# RELAY_CONTACT_BOUNCE_ELIMINATOR_REV_2.net
KiCad netlist of a schematic drawn in EAGLE
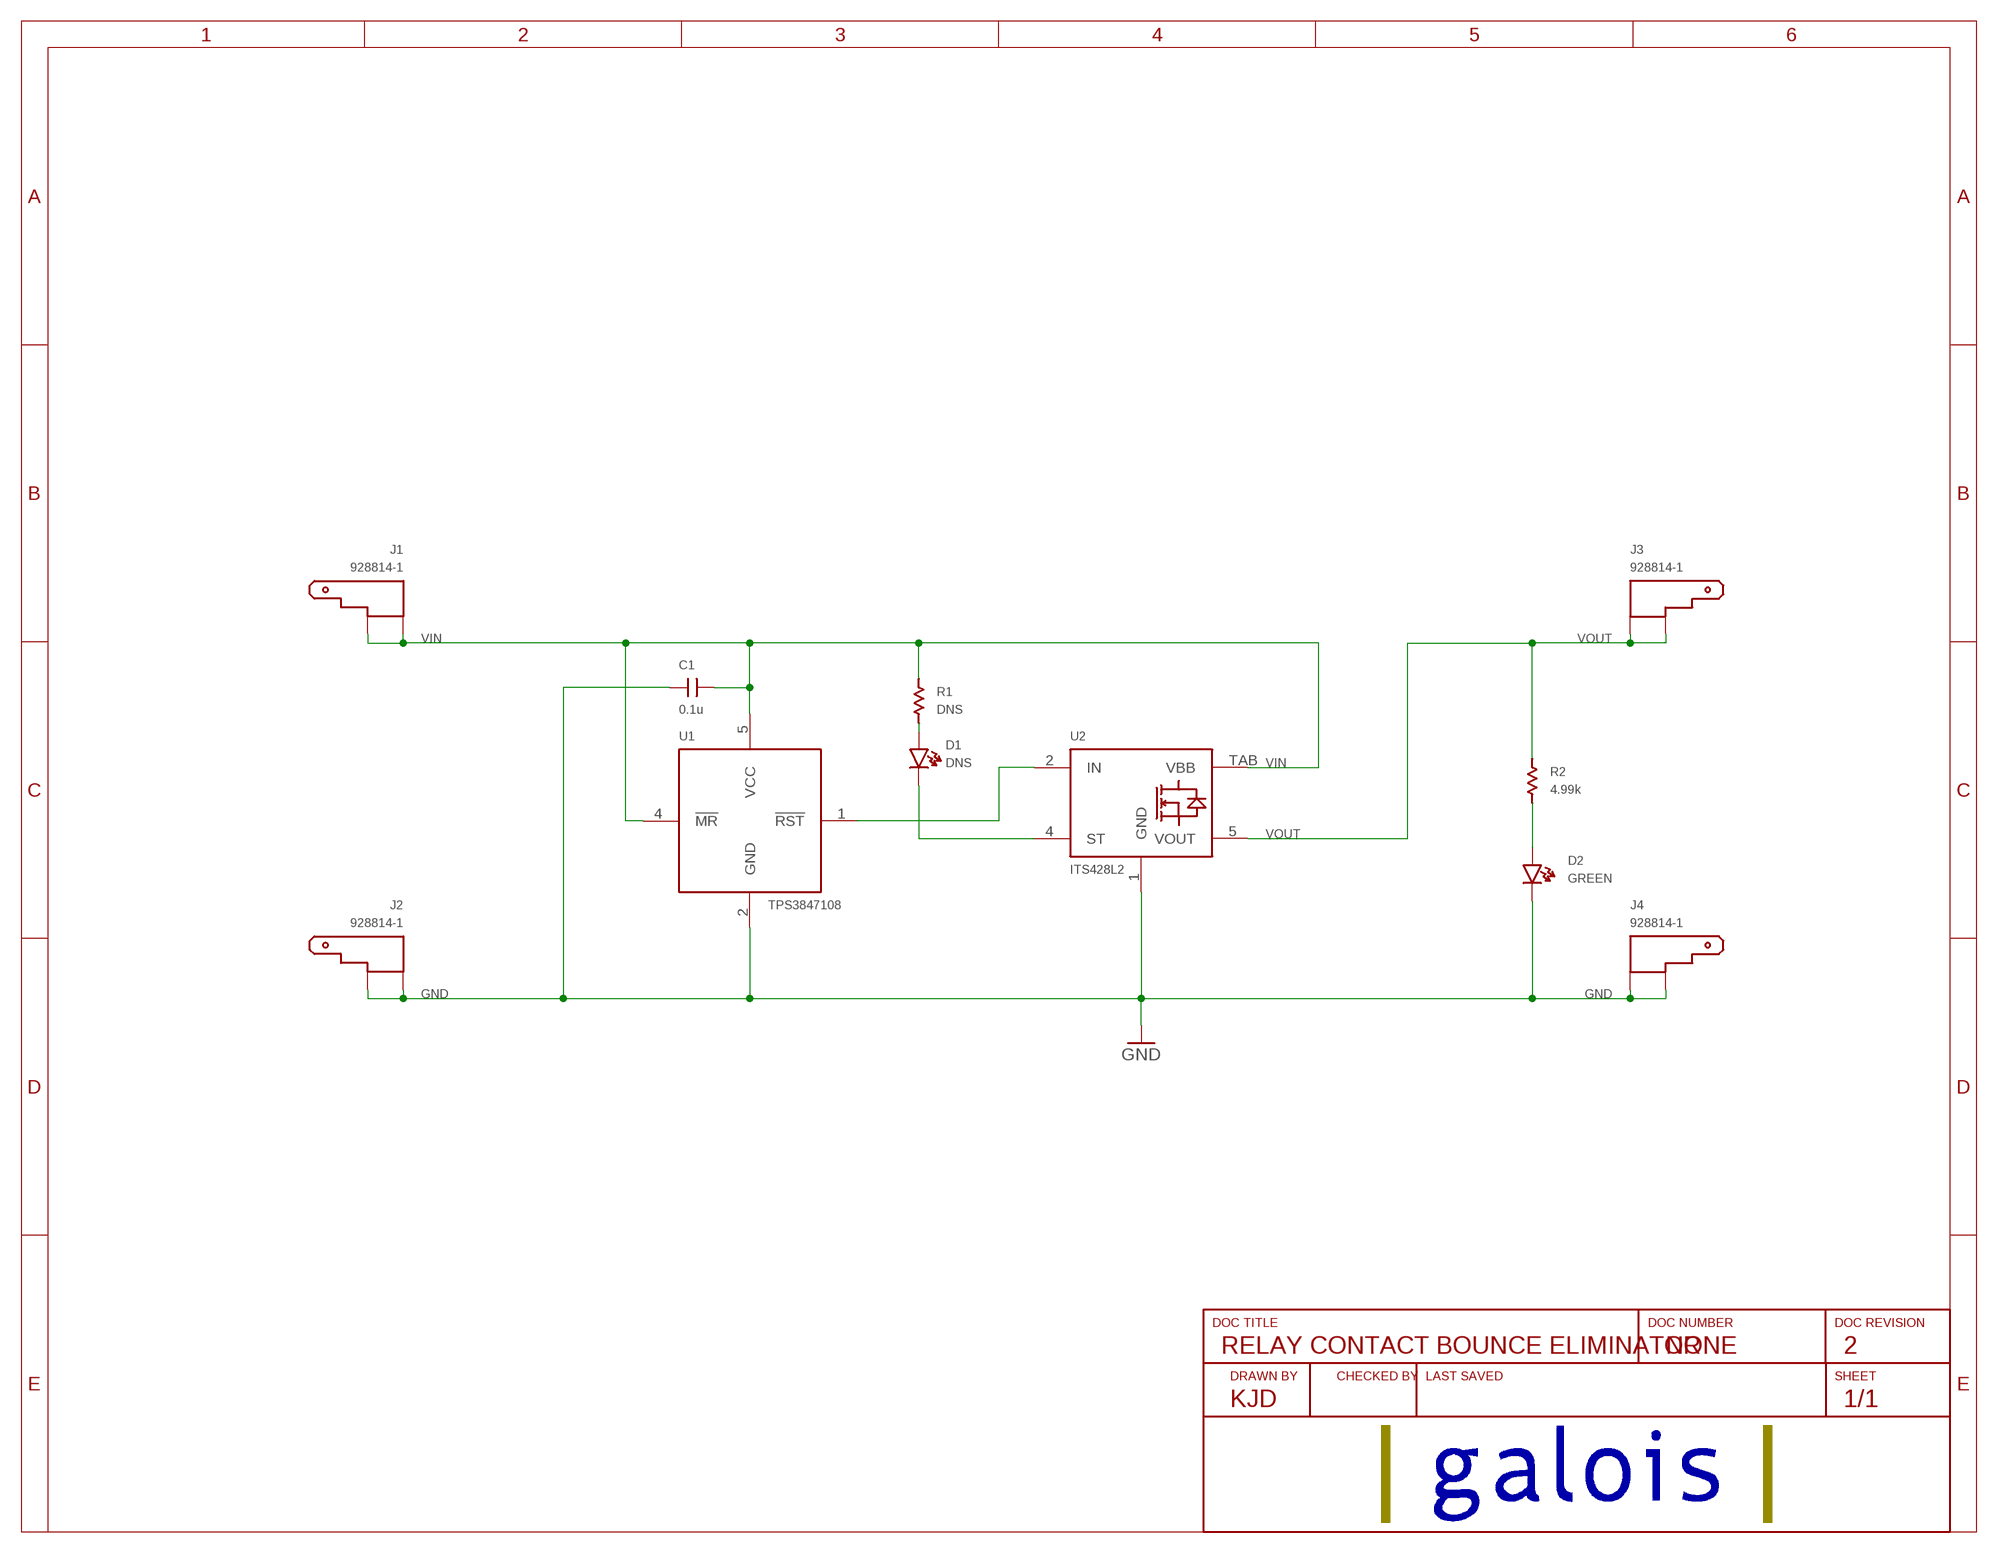
[diagram p0: schematic, sheet 1]

(export (version "E")
  (design (tool "Eeschema 10.0.6"))
  (components
    (comp (ref "C1")
      (value "0.1u")
      (footprint "eagle-import:EIA0603")
      (fields (field (name "MPN") "CL10B104KB8NNNC"))
      (libsource (lib "eagle-import") (part "C_SMDC0603"))
    )
    (comp (ref "D1")
      (value "DNS")
      (footprint "eagle-import:EIA0603_LED")
      (fields (field (name "MPN") "DNS"))
      (libsource (lib "eagle-import") (part "LED_SMD"))
    )
    (comp (ref "D2")
      (value "GREEN")
      (footprint "eagle-import:EIA0603_LED")
      (fields (field (name "MPN") "LG Q396-PS-35"))
      (libsource (lib "eagle-import") (part "LED_SMD"))
    )
    (comp (ref "J1")
      (value "928814-1")
      (footprint "eagle-import:FASTON_MALE_SERIES_250_THRU_R_A")
      (fields (field (name "MPN") "928814-1"))
      (libsource (lib "eagle-import") (part "FASTON_PCB_THRU_R/A"))
    )
    (comp (ref "J2")
      (value "928814-1")
      (footprint "eagle-import:FASTON_MALE_SERIES_250_THRU_R_A")
      (fields (field (name "MPN") "928814-1"))
      (libsource (lib "eagle-import") (part "FASTON_PCB_THRU_R/A"))
    )
    (comp (ref "J3")
      (value "928814-1")
      (footprint "eagle-import:FASTON_MALE_SERIES_250_THRU_R_A")
      (fields (field (name "MPN") "928814-1"))
      (libsource (lib "eagle-import") (part "FASTON_PCB_THRU_R/A"))
    )
    (comp (ref "J4")
      (value "928814-1")
      (footprint "eagle-import:FASTON_MALE_SERIES_250_THRU_R_A")
      (fields (field (name "MPN") "928814-1"))
      (libsource (lib "eagle-import") (part "FASTON_PCB_THRU_R/A"))
    )
    (comp (ref "R1")
      (value "DNS")
      (footprint "eagle-import:EIA0603")
      (fields (field (name "MPN") "DNS"))
      (libsource (lib "eagle-import") (part "R_SMDR0603"))
    )
    (comp (ref "R2")
      (value "4.99k")
      (footprint "eagle-import:EIA0603")
      (fields (field (name "MPN") "ERJ-3EKF4991V"))
      (libsource (lib "eagle-import") (part "R_SMDR0603"))
    )
    (comp (ref "U1")
      (value "TPS3847108")
      (footprint "eagle-import:SOT23-5")
      (fields (field (name "MPN") "TPS3847108DBVR"))
      (libsource (lib "eagle-import") (part "TPS3847"))
    )
    (comp (ref "U2")
      (value "ITS428L2")
      (footprint "eagle-import:PG-TO252-5-11")
      (fields (field (name "MPN") "ITS428L2ATMA1"))
      (libsource (lib "eagle-import") (part "ITS428L2"))
    )
  )
  (nets
    (net (code "1") (name "/VIN") (class "Default")
      (node (ref "C1") (pin "P$2") (pinfunction "P$2_P$2") (pintype "passive"))
      (node (ref "J1") (pin "1") (pinfunction "1_1") (pintype "bidirectional"))
      (node (ref "J1") (pin "2") (pinfunction "2_2") (pintype "bidirectional"))
      (node (ref "R1") (pin "P$2") (pinfunction "P$2_P$2") (pintype "passive"))
      (node (ref "U1") (pin "4") (pinfunction "~{MR}_4") (pintype "bidirectional"))
      (node (ref "U1") (pin "5") (pinfunction "VCC_5") (pintype "bidirectional"))
      (node (ref "U2") (pin "TAB") (pinfunction "VBB_TAB") (pintype "bidirectional"))
    )
    (net (code "2") (name "/VOUT") (class "Default")
      (node (ref "J3") (pin "1") (pinfunction "1_1") (pintype "bidirectional"))
      (node (ref "J3") (pin "2") (pinfunction "2_2") (pintype "bidirectional"))
      (node (ref "R2") (pin "P$2") (pinfunction "P$2_P$2") (pintype "passive"))
      (node (ref "U2") (pin "5") (pinfunction "VOUT_5") (pintype "bidirectional"))
    )
    (net (code "3") (name "GND") (class "Default")
      (node (ref "C1") (pin "P$1") (pinfunction "P$1_P$1") (pintype "passive"))
      (node (ref "D2") (pin "C") (pinfunction "C_C") (pintype "passive"))
      (node (ref "J2") (pin "1") (pinfunction "1_1") (pintype "bidirectional"))
      (node (ref "J2") (pin "2") (pinfunction "2_2") (pintype "bidirectional"))
      (node (ref "J4") (pin "1") (pinfunction "1_1") (pintype "bidirectional"))
      (node (ref "J4") (pin "2") (pinfunction "2_2") (pintype "bidirectional"))
      (node (ref "U1") (pin "2") (pinfunction "GND_2") (pintype "bidirectional"))
      (node (ref "U2") (pin "1") (pinfunction "GND_1") (pintype "bidirectional"))
    )
    (net (code "4") (name "Net-(D1-PadA)") (class "Default")
      (node (ref "D1") (pin "A") (pinfunction "A_A") (pintype "passive"))
      (node (ref "R1") (pin "P$1") (pinfunction "P$1_P$1") (pintype "passive"))
    )
    (net (code "5") (name "Net-(D2-PadA)") (class "Default")
      (node (ref "D2") (pin "A") (pinfunction "A_A") (pintype "passive"))
      (node (ref "R2") (pin "P$1") (pinfunction "P$1_P$1") (pintype "passive"))
    )
    (net (code "6") (name "Net-(U1-~{RST})") (class "Default")
      (node (ref "U1") (pin "1") (pinfunction "~{RST}_1") (pintype "bidirectional"))
      (node (ref "U2") (pin "2") (pinfunction "IN_2") (pintype "bidirectional"))
    )
    (net (code "7") (name "Net-(U2-ST)") (class "Default")
      (node (ref "D1") (pin "C") (pinfunction "C_C") (pintype "passive"))
      (node (ref "U2") (pin "4") (pinfunction "ST_4") (pintype "bidirectional"))
    )
  )
)
